# Expanders.net
KiCad netlist of a schematic drawn in Altium Designer
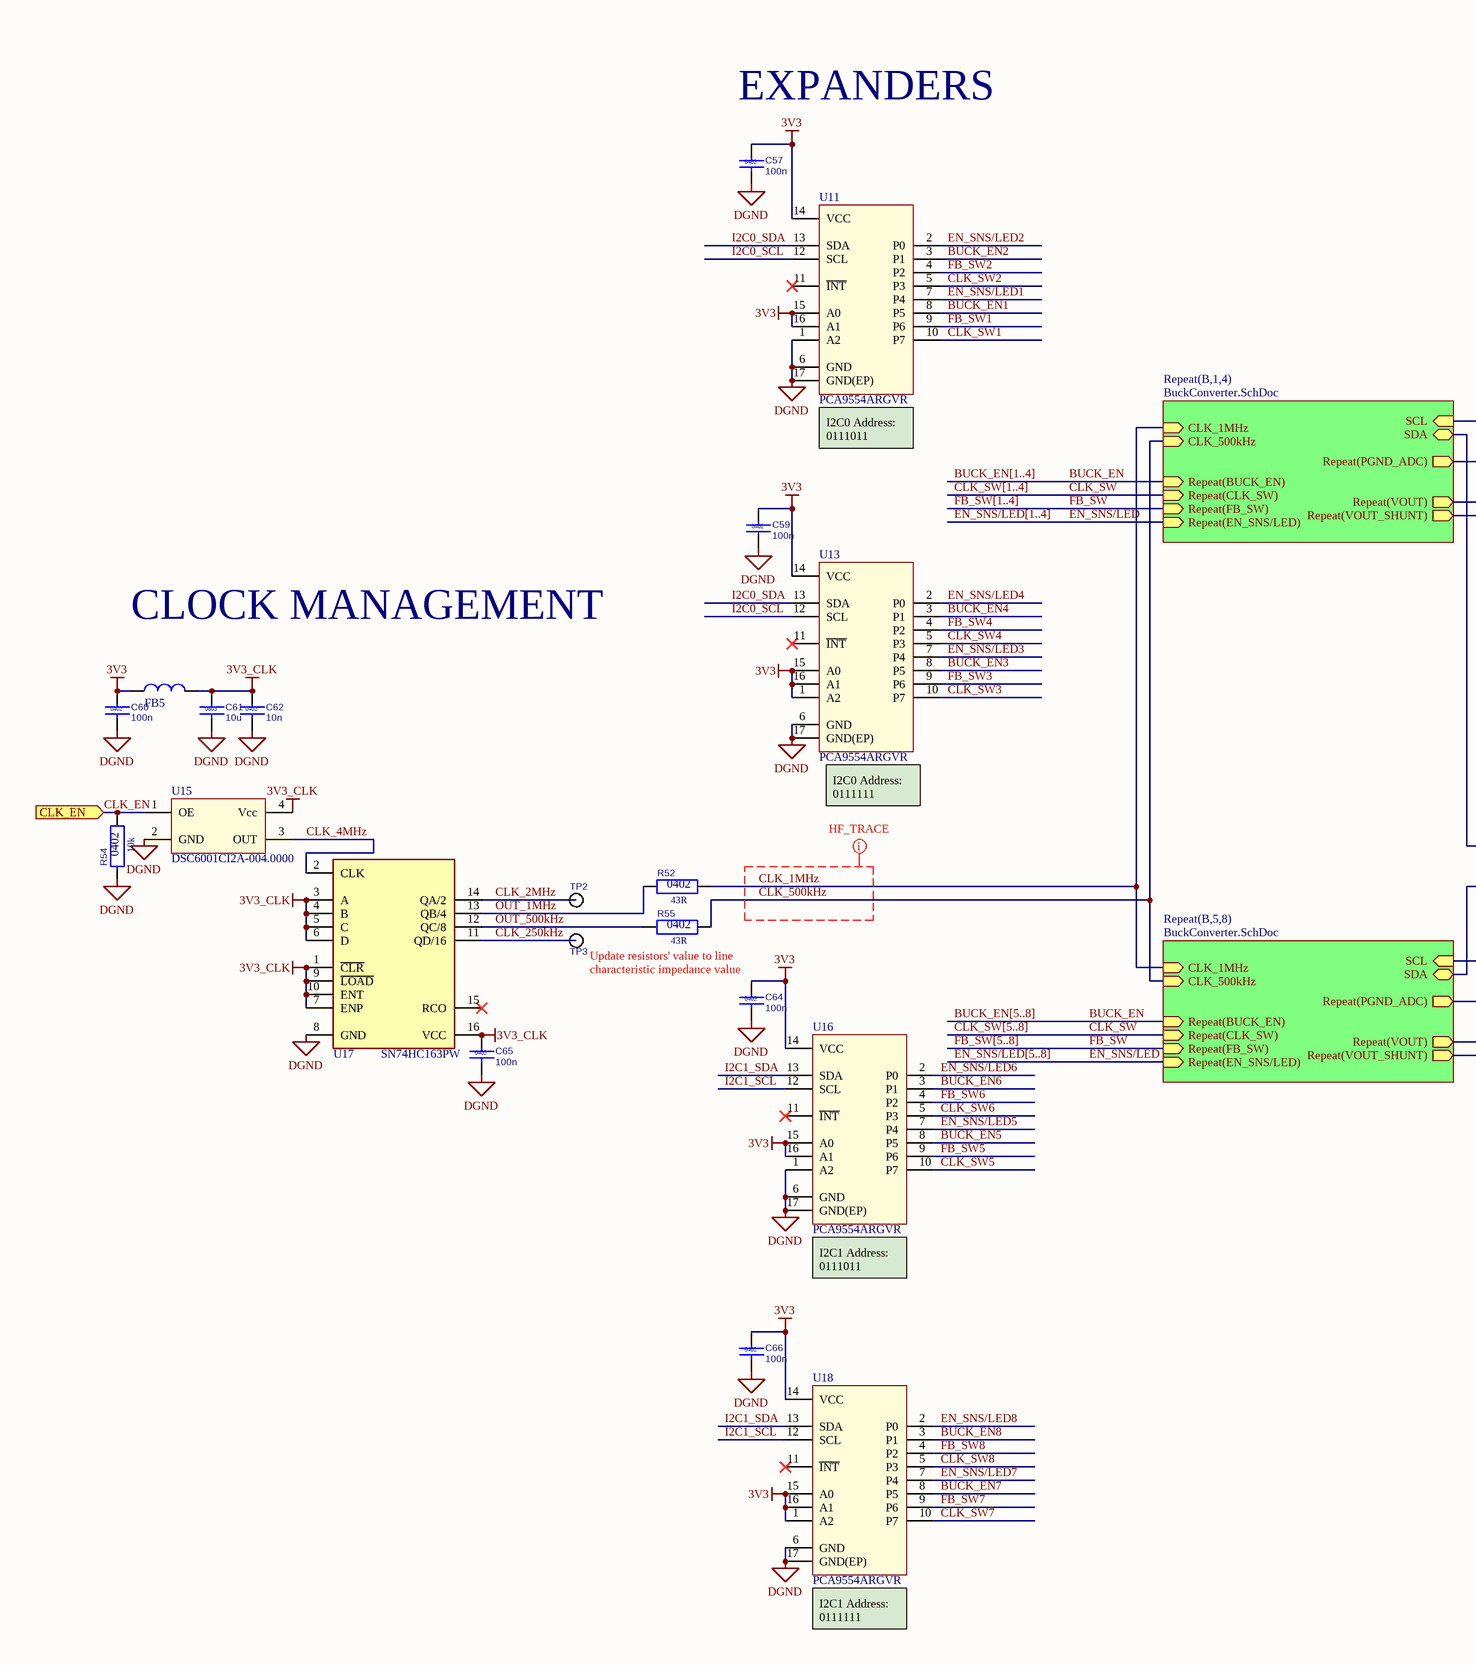
[diagram p0: Expanders.SchDoc, left]
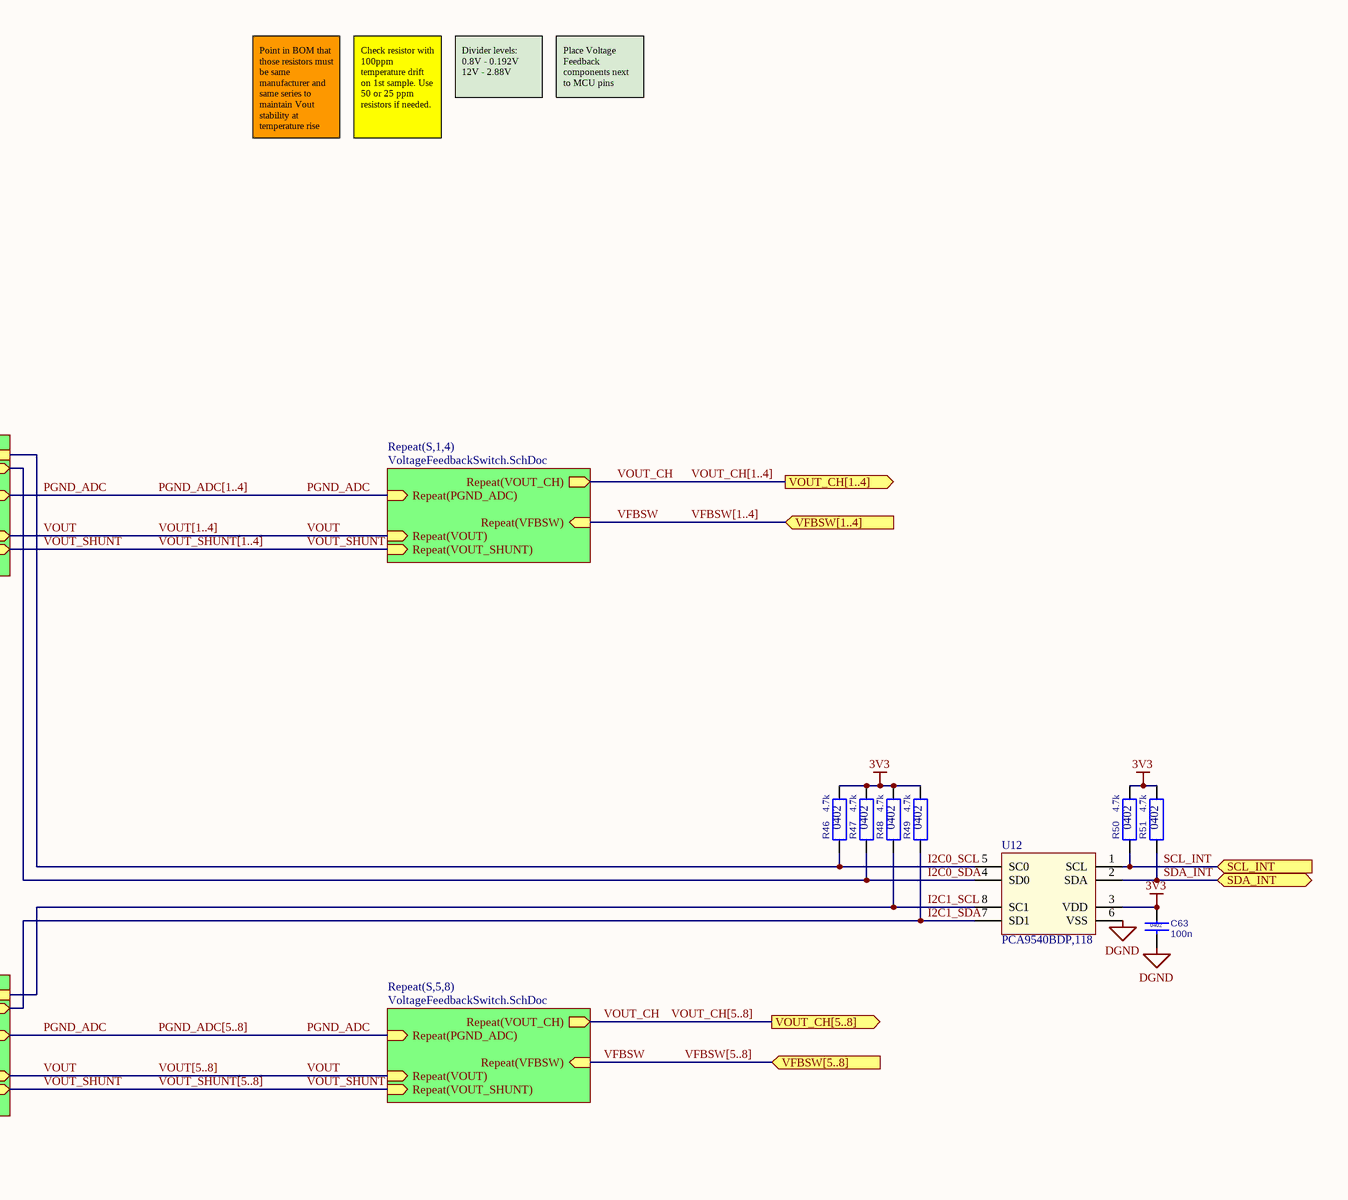
[diagram p1: Expanders.SchDoc, right]

(export (version "E")
  (design (tool "Eeschema 10.0.6"))
  (components
    (comp (ref "C57")
      (value "100n")
      (footprint "CC0402M")
      (description "Chip ceramic capacitor")
      (fields
        (field (name "CASE") "0402")
        (field (name "PARTNUMBER") "CC0402K-X7R-25V-100N-M")
        (field (name "MANUFACTURER") "Murata")
        (field (name "PUBLISHER") "alexey.savchenko")
      )
      (libsource (lib "AltiumLib") (part "Capacitor_nonpolar"))
    )
    (comp (ref "C59")
      (value "100n")
      (footprint "CC0402M")
      (description "Chip ceramic capacitor")
      (fields
        (field (name "CASE") "0402")
        (field (name "PARTNUMBER") "CC0402K-X7R-25V-100N-M")
        (field (name "MANUFACTURER") "Murata")
        (field (name "PUBLISHER") "alexey.savchenko")
      )
      (libsource (lib "AltiumLib") (part "Capacitor_nonpolar"))
    )
    (comp (ref "C60")
      (value "100n")
      (footprint "CC0402M")
      (description "Chip ceramic capacitor")
      (fields
        (field (name "CASE") "0402")
        (field (name "PARTNUMBER") "CC0402K-X7R-25V-100N-M")
        (field (name "MANUFACTURER") "Murata")
        (field (name "PUBLISHER") "alexey.savchenko")
      )
      (libsource (lib "AltiumLib") (part "Capacitor_nonpolar"))
    )
    (comp (ref "C61")
      (value "10u")
      (footprint "CC0805M")
      (description "Chip ceramic capacitor")
      (fields
        (field (name "CASE") "0805")
        (field (name "PARTNUMBER") "CC0805K-X7R-6V3-10U-M")
        (field (name "MANUFACTURER") "Samsung")
        (field (name "PUBLISHER") "alexey.savchenko")
      )
      (libsource (lib "AltiumLib") (part "Capacitor_nonpolar"))
    )
    (comp (ref "C62")
      (value "10n")
      (footprint "CC0402M")
      (description "Chip ceramic capacitor")
      (fields
        (field (name "CASE") "0402")
        (field (name "PARTNUMBER") "CC0402K-X7R-50V-10N-M")
        (field (name "MANUFACTURER") "Yageo")
        (field (name "PUBLISHER") "alexey.savchenko")
      )
      (libsource (lib "AltiumLib") (part "Capacitor_nonpolar"))
    )
    (comp (ref "C63")
      (value "100n")
      (footprint "CC0402M")
      (description "Chip ceramic capacitor")
      (fields
        (field (name "CASE") "0402")
        (field (name "PARTNUMBER") "CC0402K-X7R-25V-100N-M")
        (field (name "MANUFACTURER") "Murata")
        (field (name "PUBLISHER") "alexey.savchenko")
      )
      (libsource (lib "AltiumLib") (part "Capacitor_nonpolar"))
    )
    (comp (ref "C64")
      (value "100n")
      (footprint "CC0402M")
      (description "Chip ceramic capacitor")
      (fields
        (field (name "CASE") "0402")
        (field (name "PARTNUMBER") "CC0402K-X7R-25V-100N-M")
        (field (name "MANUFACTURER") "Murata")
        (field (name "PUBLISHER") "alexey.savchenko")
      )
      (libsource (lib "AltiumLib") (part "Capacitor_nonpolar"))
    )
    (comp (ref "C65")
      (value "100n")
      (footprint "CC0402M")
      (description "Chip ceramic capacitor")
      (fields
        (field (name "CASE") "0402")
        (field (name "PARTNUMBER") "CC0402K-X7R-25V-100N-M")
        (field (name "MANUFACTURER") "Murata")
        (field (name "PUBLISHER") "alexey.savchenko")
      )
      (libsource (lib "AltiumLib") (part "Capacitor_nonpolar"))
    )
    (comp (ref "C66")
      (value "100n")
      (footprint "CC0402M")
      (description "Chip ceramic capacitor")
      (fields
        (field (name "CASE") "0402")
        (field (name "PARTNUMBER") "CC0402K-X7R-25V-100N-M")
        (field (name "MANUFACTURER") "Murata")
        (field (name "PUBLISHER") "alexey.savchenko")
      )
      (libsource (lib "AltiumLib") (part "Capacitor_nonpolar"))
    )
    (comp (ref "FB5")
      (value "BLM18HG102SN1D")
      (footprint "FB0603M")
      (description "FERRITE BEAD 1 KOHM 0603 1LN")
      (fields (field (name "MANUFACTURER") "Murata") (field (name "PUBLISHER") "alexey.savchenko"))
      (libsource (lib "AltiumLib") (part "FerriteBead"))
    )
    (comp (ref "R46")
      (value "4.7k")
      (footprint "RC0402M")
      (description "Chip resistor")
      (fields
        (field (name "CASE") "0402")
        (field (name "PARTNUMBER") "RC0402F-4K7-M")
        (field (name "POWER") "0.063W")
        (field (name "PUBLISHER") "alexey.savchenko")
      )
      (libsource (lib "AltiumLib") (part "Resistor"))
    )
    (comp (ref "R47")
      (value "4.7k")
      (footprint "RC0402M")
      (description "Chip resistor")
      (fields
        (field (name "CASE") "0402")
        (field (name "PARTNUMBER") "RC0402F-4K7-M")
        (field (name "POWER") "0.063W")
        (field (name "PUBLISHER") "alexey.savchenko")
      )
      (libsource (lib "AltiumLib") (part "Resistor"))
    )
    (comp (ref "R48")
      (value "4.7k")
      (footprint "RC0402M")
      (description "Chip resistor")
      (fields
        (field (name "CASE") "0402")
        (field (name "PARTNUMBER") "RC0402F-4K7-M")
        (field (name "POWER") "0.063W")
        (field (name "PUBLISHER") "alexey.savchenko")
      )
      (libsource (lib "AltiumLib") (part "Resistor"))
    )
    (comp (ref "R49")
      (value "4.7k")
      (footprint "RC0402M")
      (description "Chip resistor")
      (fields
        (field (name "CASE") "0402")
        (field (name "PARTNUMBER") "RC0402F-4K7-M")
        (field (name "POWER") "0.063W")
        (field (name "PUBLISHER") "alexey.savchenko")
      )
      (libsource (lib "AltiumLib") (part "Resistor"))
    )
    (comp (ref "R50")
      (value "4.7k")
      (footprint "RC0402M")
      (description "Chip resistor")
      (fields
        (field (name "CASE") "0402")
        (field (name "PARTNUMBER") "RC0402F-4K7-M")
        (field (name "POWER") "0.063W")
        (field (name "PUBLISHER") "alexey.savchenko")
      )
      (libsource (lib "AltiumLib") (part "Resistor"))
    )
    (comp (ref "R51")
      (value "4.7k")
      (footprint "RC0402M")
      (description "Chip resistor")
      (fields
        (field (name "CASE") "0402")
        (field (name "PARTNUMBER") "RC0402F-4K7-M")
        (field (name "POWER") "0.063W")
        (field (name "PUBLISHER") "alexey.savchenko")
      )
      (libsource (lib "AltiumLib") (part "Resistor"))
    )
    (comp (ref "R52")
      (value "43R")
      (footprint "RC0402M")
      (description "Chip resistor")
      (fields
        (field (name "CASE") "0402")
        (field (name "PARTNUMBER") "RC0402F-43R-M")
        (field (name "POWER") "0.063W")
        (field (name "PUBLISHER") "alexey.savchenko")
      )
      (libsource (lib "AltiumLib") (part "Resistor"))
    )
    (comp (ref "R54")
      (value "10k")
      (footprint "RC0402M")
      (description "Chip resistor")
      (fields
        (field (name "CASE") "0402")
        (field (name "PARTNUMBER") "RC0402F-10K-M")
        (field (name "MANUFACTURER") "Yageo")
        (field (name "PUBLISHER") "alexey.savchenko")
      )
      (libsource (lib "AltiumLib") (part "Resistor"))
    )
    (comp (ref "R55")
      (value "43R")
      (footprint "RC0402M")
      (description "Chip resistor")
      (fields
        (field (name "CASE") "0402")
        (field (name "PARTNUMBER") "RC0402F-43R-M")
        (field (name "POWER") "0.063W")
        (field (name "PUBLISHER") "alexey.savchenko")
      )
      (libsource (lib "AltiumLib") (part "Resistor"))
    )
    (comp (ref "TP2")
      (value "TEST_POINT")
      (footprint "TEST_POINT_SMALL")
      (description "Test point")
      (fields
        (field (name "PARTNUMBER") "TEST_POINT_SMALL")
        (field (name "MANUFACTURER") "NULL")
        (field (name "PUBLISHER") "alexey.savchenko")
      )
      (libsource (lib "AltiumLib") (part "TEST_POINT"))
    )
    (comp (ref "TP3")
      (value "TEST_POINT")
      (footprint "TEST_POINT_SMALL")
      (description "Test point")
      (fields
        (field (name "PARTNUMBER") "TEST_POINT_SMALL")
        (field (name "MANUFACTURER") "NULL")
        (field (name "PUBLISHER") "alexey.savchenko")
      )
      (libsource (lib "AltiumLib") (part "TEST_POINT"))
    )
    (comp (ref "U11")
      (value "PCA9554ARGVR")
      (footprint "VQFN-16(RGV)")
      (description "I/O Expander 8 I²C, SMBus 400kHz 16-VQFN (4x4)")
      (fields (field (name "MANUFACTURER") "TI") (field (name "PUBLISHER") "alexey.savchenko"))
      (libsource (lib "AltiumLib") (part "PCA9554ARGVR"))
    )
    (comp (ref "U12")
      (value "PCA9540BDP,118")
      (footprint "TSSOP-8")
      (description "IC INTERFACE SPECIALIZED 8TSSOP")
      (fields (field (name "MANUFACTURER") "NXP") (field (name "PUBLISHER") "alexey.savchenko"))
      (libsource (lib "AltiumLib") (part "PCA9540B"))
    )
    (comp (ref "U13")
      (value "PCA9554ARGVR")
      (footprint "VQFN-16(RGV)")
      (description "I/O Expander 8 I²C, SMBus 400kHz 16-VQFN (4x4)")
      (fields (field (name "MANUFACTURER") "TI") (field (name "PUBLISHER") "alexey.savchenko"))
      (libsource (lib "AltiumLib") (part "PCA9554ARGVR"))
    )
    (comp (ref "U15")
      (value "DSC6001CI2A-004.0000")
      (footprint "CDFN3225-4LD")
      (description "4MHz XO (Standard) CMOS Oscillator 1.8V ~ 3.3V Enable/Disable 4-SMD, No Lead")
      (fields (field (name "MANUFACTURER") "Microchip") (field (name "PUBLISHER") "alexey.savchenko"))
      (libsource (lib "AltiumLib") (part "DSC6001"))
    )
    (comp (ref "U16")
      (value "PCA9554ARGVR")
      (footprint "VQFN-16(RGV)")
      (description "I/O Expander 8 I²C, SMBus 400kHz 16-VQFN (4x4)")
      (fields (field (name "MANUFACTURER") "TI") (field (name "PUBLISHER") "alexey.savchenko"))
      (libsource (lib "AltiumLib") (part "PCA9554ARGVR"))
    )
    (comp (ref "U17")
      (value "SN74HC163PW")
      (footprint "TSSOP-16")
      (description "Counter IC Binary Counter 1 Element 4 Bit Positive Edge 16-TSSOP")
      (fields (field (name "MANUFACTURER") "TI") (field (name "PUBLISHER") "alexey.savchenko"))
      (libsource (lib "AltiumLib") (part "74HC163PW"))
    )
    (comp (ref "U18")
      (value "PCA9554ARGVR")
      (footprint "VQFN-16(RGV)")
      (description "I/O Expander 8 I²C, SMBus 400kHz 16-VQFN (4x4)")
      (fields (field (name "MANUFACTURER") "TI") (field (name "PUBLISHER") "alexey.savchenko"))
      (libsource (lib "AltiumLib") (part "PCA9554ARGVR"))
    )
  )
  (nets
    (net (code "50") (name "/BUCK_EN1") (class "Default")
      (node (ref "U11") (pin "8") (pinfunction "P5_8") (pintype "passive"))
    )
    (net (code "51") (name "/BUCK_EN2") (class "Default")
      (node (ref "U11") (pin "3") (pinfunction "P1_3") (pintype "passive"))
    )
    (net (code "52") (name "/BUCK_EN3") (class "Default")
      (node (ref "U13") (pin "8") (pinfunction "P5_8") (pintype "passive"))
    )
    (net (code "53") (name "/BUCK_EN4") (class "Default")
      (node (ref "U13") (pin "3") (pinfunction "P1_3") (pintype "passive"))
    )
    (net (code "54") (name "/BUCK_EN5") (class "Default")
      (node (ref "U16") (pin "8") (pinfunction "P5_8") (pintype "passive"))
    )
    (net (code "55") (name "/BUCK_EN6") (class "Default")
      (node (ref "U16") (pin "3") (pinfunction "P1_3") (pintype "passive"))
    )
    (net (code "56") (name "/BUCK_EN7") (class "Default")
      (node (ref "U18") (pin "8") (pinfunction "P5_8") (pintype "passive"))
    )
    (net (code "57") (name "/BUCK_EN8") (class "Default")
      (node (ref "U18") (pin "3") (pinfunction "P1_3") (pintype "passive"))
    )
    (net (code "60") (name "/CLK_1MHz") (class "Default")
      (node (ref "R52") (pin "2") (pinfunction "2_2") (pintype "passive"))
    )
    (net (code "61") (name "/CLK_2MHz") (class "Default")
      (node (ref "TP2") (pin "0") (pinfunction "0_0") (pintype "passive"))
      (node (ref "U17") (pin "14") (pinfunction "QA/2_14") (pintype "passive"))
    )
    (net (code "62") (name "/CLK_4MHz") (class "Default")
      (node (ref "U15") (pin "3") (pinfunction "OUT_3") (pintype "passive"))
      (node (ref "U17") (pin "2") (pinfunction "CLK_2") (pintype "passive"))
    )
    (net (code "63") (name "/CLK_250kHz") (class "Default")
      (node (ref "TP3") (pin "0") (pinfunction "0_0") (pintype "passive"))
      (node (ref "U17") (pin "11") (pinfunction "QD/16_11") (pintype "passive"))
    )
    (net (code "64") (name "/CLK_500kHz") (class "Default")
      (node (ref "R55") (pin "2") (pinfunction "2_2") (pintype "passive"))
    )
    (net (code "65") (name "/CLK_EN") (class "Default")
      (node (ref "R54") (pin "2") (pinfunction "2_2") (pintype "passive"))
      (node (ref "U15") (pin "1") (pinfunction "OE_1") (pintype "passive"))
    )
    (net (code "67") (name "/CLK_SW1") (class "Default")
      (node (ref "U11") (pin "10") (pinfunction "P7_10") (pintype "passive"))
    )
    (net (code "68") (name "/CLK_SW2") (class "Default")
      (node (ref "U11") (pin "5") (pinfunction "P3_5") (pintype "passive"))
    )
    (net (code "69") (name "/CLK_SW3") (class "Default")
      (node (ref "U13") (pin "10") (pinfunction "P7_10") (pintype "passive"))
    )
    (net (code "70") (name "/CLK_SW4") (class "Default")
      (node (ref "U13") (pin "5") (pinfunction "P3_5") (pintype "passive"))
    )
    (net (code "71") (name "/CLK_SW5") (class "Default")
      (node (ref "U16") (pin "10") (pinfunction "P7_10") (pintype "passive"))
    )
    (net (code "72") (name "/CLK_SW6") (class "Default")
      (node (ref "U16") (pin "5") (pinfunction "P3_5") (pintype "passive"))
    )
    (net (code "73") (name "/CLK_SW7") (class "Default")
      (node (ref "U18") (pin "10") (pinfunction "P7_10") (pintype "passive"))
    )
    (net (code "74") (name "/CLK_SW8") (class "Default")
      (node (ref "U18") (pin "5") (pinfunction "P3_5") (pintype "passive"))
    )
    (net (code "78") (name "/EN_SNS{slash}LED1") (class "Default")
      (node (ref "U11") (pin "7") (pinfunction "P4_7") (pintype "passive"))
    )
    (net (code "79") (name "/EN_SNS{slash}LED2") (class "Default")
      (node (ref "U11") (pin "2") (pinfunction "P0_2") (pintype "passive"))
    )
    (net (code "80") (name "/EN_SNS{slash}LED3") (class "Default")
      (node (ref "U13") (pin "7") (pinfunction "P4_7") (pintype "passive"))
    )
    (net (code "81") (name "/EN_SNS{slash}LED4") (class "Default")
      (node (ref "U13") (pin "2") (pinfunction "P0_2") (pintype "passive"))
    )
    (net (code "82") (name "/EN_SNS{slash}LED5") (class "Default")
      (node (ref "U16") (pin "7") (pinfunction "P4_7") (pintype "passive"))
    )
    (net (code "83") (name "/EN_SNS{slash}LED6") (class "Default")
      (node (ref "U16") (pin "2") (pinfunction "P0_2") (pintype "passive"))
    )
    (net (code "84") (name "/EN_SNS{slash}LED7") (class "Default")
      (node (ref "U18") (pin "7") (pinfunction "P4_7") (pintype "passive"))
    )
    (net (code "85") (name "/EN_SNS{slash}LED8") (class "Default")
      (node (ref "U18") (pin "2") (pinfunction "P0_2") (pintype "passive"))
    )
    (net (code "89") (name "/FB_SW1") (class "Default")
      (node (ref "U11") (pin "9") (pinfunction "P6_9") (pintype "passive"))
    )
    (net (code "90") (name "/FB_SW2") (class "Default")
      (node (ref "U11") (pin "4") (pinfunction "P2_4") (pintype "passive"))
    )
    (net (code "91") (name "/FB_SW3") (class "Default")
      (node (ref "U13") (pin "9") (pinfunction "P6_9") (pintype "passive"))
    )
    (net (code "92") (name "/FB_SW4") (class "Default")
      (node (ref "U13") (pin "4") (pinfunction "P2_4") (pintype "passive"))
    )
    (net (code "93") (name "/FB_SW5") (class "Default")
      (node (ref "U16") (pin "9") (pinfunction "P6_9") (pintype "passive"))
    )
    (net (code "94") (name "/FB_SW6") (class "Default")
      (node (ref "U16") (pin "4") (pinfunction "P2_4") (pintype "passive"))
    )
    (net (code "95") (name "/FB_SW7") (class "Default")
      (node (ref "U18") (pin "9") (pinfunction "P6_9") (pintype "passive"))
    )
    (net (code "96") (name "/FB_SW8") (class "Default")
      (node (ref "U18") (pin "4") (pinfunction "P2_4") (pintype "passive"))
    )
    (net (code "99") (name "/I2C0_SCL") (class "Default")
      (node (ref "R46") (pin "1") (pinfunction "1_1") (pintype "passive"))
      (node (ref "U11") (pin "12") (pinfunction "SCL_12") (pintype "passive"))
      (node (ref "U12") (pin "5") (pinfunction "SC0_5") (pintype "passive"))
      (node (ref "U13") (pin "12") (pinfunction "SCL_12") (pintype "passive"))
    )
    (net (code "100") (name "/I2C0_SDA") (class "Default")
      (node (ref "R47") (pin "1") (pinfunction "1_1") (pintype "passive"))
      (node (ref "U11") (pin "13") (pinfunction "SDA_13") (pintype "passive"))
      (node (ref "U12") (pin "4") (pinfunction "SD0_4") (pintype "passive"))
      (node (ref "U13") (pin "13") (pinfunction "SDA_13") (pintype "passive"))
    )
    (net (code "101") (name "/I2C1_SCL") (class "Default")
      (node (ref "R48") (pin "1") (pinfunction "1_1") (pintype "passive"))
      (node (ref "U12") (pin "8") (pinfunction "SC1_8") (pintype "passive"))
      (node (ref "U16") (pin "12") (pinfunction "SCL_12") (pintype "passive"))
      (node (ref "U18") (pin "12") (pinfunction "SCL_12") (pintype "passive"))
    )
    (net (code "102") (name "/I2C1_SDA") (class "Default")
      (node (ref "R49") (pin "1") (pinfunction "1_1") (pintype "passive"))
      (node (ref "U12") (pin "7") (pinfunction "SD1_7") (pintype "passive"))
      (node (ref "U16") (pin "13") (pinfunction "SDA_13") (pintype "passive"))
      (node (ref "U18") (pin "13") (pinfunction "SDA_13") (pintype "passive"))
    )
    (net (code "103") (name "/OUT_1MHz") (class "Default")
      (node (ref "R52") (pin "1") (pinfunction "1_1") (pintype "passive"))
      (node (ref "U17") (pin "13") (pinfunction "QB/4_13") (pintype "passive"))
    )
    (net (code "104") (name "/OUT_500kHz") (class "Default")
      (node (ref "R55") (pin "1") (pinfunction "1_1") (pintype "passive"))
      (node (ref "U17") (pin "12") (pinfunction "QC/8_12") (pintype "passive"))
    )
    (net (code "108") (name "/SCL_INT") (class "Default")
      (node (ref "R50") (pin "1") (pinfunction "1_1") (pintype "passive"))
      (node (ref "U12") (pin "1") (pinfunction "SCL_1") (pintype "passive"))
    )
    (net (code "109") (name "/SDA_INT") (class "Default")
      (node (ref "R51") (pin "1") (pinfunction "1_1") (pintype "passive"))
      (node (ref "U12") (pin "2") (pinfunction "SDA_2") (pintype "passive"))
    )
    (net (code "122") (name "3V3") (class "Default")
      (node (ref "C57") (pin "1") (pinfunction "1_1") (pintype "passive"))
      (node (ref "C59") (pin "1") (pinfunction "1_1") (pintype "passive"))
      (node (ref "C60") (pin "1") (pinfunction "1_1") (pintype "passive"))
      (node (ref "C63") (pin "1") (pinfunction "1_1") (pintype "passive"))
      (node (ref "C64") (pin "1") (pinfunction "1_1") (pintype "passive"))
      (node (ref "C66") (pin "1") (pinfunction "1_1") (pintype "passive"))
      (node (ref "FB5") (pin "1") (pinfunction "1_1") (pintype "passive"))
      (node (ref "R46") (pin "2") (pinfunction "2_2") (pintype "passive"))
      (node (ref "R47") (pin "2") (pinfunction "2_2") (pintype "passive"))
      (node (ref "R48") (pin "2") (pinfunction "2_2") (pintype "passive"))
      (node (ref "R49") (pin "2") (pinfunction "2_2") (pintype "passive"))
      (node (ref "R50") (pin "2") (pinfunction "2_2") (pintype "passive"))
      (node (ref "R51") (pin "2") (pinfunction "2_2") (pintype "passive"))
      (node (ref "U11") (pin "14") (pinfunction "VCC_14") (pintype "passive"))
      (node (ref "U11") (pin "15") (pinfunction "A0_15") (pintype "passive"))
      (node (ref "U11") (pin "16") (pinfunction "A1_16") (pintype "passive"))
      (node (ref "U12") (pin "3") (pinfunction "VDD_3") (pintype "passive"))
      (node (ref "U13") (pin "1") (pinfunction "A2_1") (pintype "passive"))
      (node (ref "U13") (pin "14") (pinfunction "VCC_14") (pintype "passive"))
      (node (ref "U13") (pin "15") (pinfunction "A0_15") (pintype "passive"))
      (node (ref "U13") (pin "16") (pinfunction "A1_16") (pintype "passive"))
      (node (ref "U16") (pin "14") (pinfunction "VCC_14") (pintype "passive"))
      (node (ref "U16") (pin "15") (pinfunction "A0_15") (pintype "passive"))
      (node (ref "U16") (pin "16") (pinfunction "A1_16") (pintype "passive"))
      (node (ref "U18") (pin "1") (pinfunction "A2_1") (pintype "passive"))
      (node (ref "U18") (pin "14") (pinfunction "VCC_14") (pintype "passive"))
      (node (ref "U18") (pin "15") (pinfunction "A0_15") (pintype "passive"))
      (node (ref "U18") (pin "16") (pinfunction "A1_16") (pintype "passive"))
    )
    (net (code "123") (name "3V3_CLK") (class "Default")
      (node (ref "C61") (pin "1") (pinfunction "1_1") (pintype "passive"))
      (node (ref "C62") (pin "1") (pinfunction "1_1") (pintype "passive"))
      (node (ref "C65") (pin "1") (pinfunction "1_1") (pintype "passive"))
      (node (ref "FB5") (pin "2") (pinfunction "2_2") (pintype "passive"))
      (node (ref "U15") (pin "4") (pinfunction "Vcc_4") (pintype "passive"))
      (node (ref "U17") (pin "1") (pinfunction "~{CLR}_1") (pintype "passive"))
      (node (ref "U17") (pin "10") (pinfunction "ENT_10") (pintype "passive"))
      (node (ref "U17") (pin "16") (pinfunction "VCC_16") (pintype "passive"))
      (node (ref "U17") (pin "3") (pinfunction "A_3") (pintype "passive"))
      (node (ref "U17") (pin "4") (pinfunction "B_4") (pintype "passive"))
      (node (ref "U17") (pin "5") (pinfunction "C_5") (pintype "passive"))
      (node (ref "U17") (pin "6") (pinfunction "D_6") (pintype "passive"))
      (node (ref "U17") (pin "7") (pinfunction "ENP_7") (pintype "passive"))
      (node (ref "U17") (pin "9") (pinfunction "~{LOAD}_9") (pintype "passive"))
    )
    (net (code "124") (name "DGND") (class "Default")
      (node (ref "C57") (pin "2") (pinfunction "2_2") (pintype "passive"))
      (node (ref "C59") (pin "2") (pinfunction "2_2") (pintype "passive"))
      (node (ref "C60") (pin "2") (pinfunction "2_2") (pintype "passive"))
      (node (ref "C61") (pin "2") (pinfunction "2_2") (pintype "passive"))
      (node (ref "C62") (pin "2") (pinfunction "2_2") (pintype "passive"))
      (node (ref "C63") (pin "2") (pinfunction "2_2") (pintype "passive"))
      (node (ref "C64") (pin "2") (pinfunction "2_2") (pintype "passive"))
      (node (ref "C65") (pin "2") (pinfunction "2_2") (pintype "passive"))
      (node (ref "C66") (pin "2") (pinfunction "2_2") (pintype "passive"))
      (node (ref "R54") (pin "1") (pinfunction "1_1") (pintype "passive"))
      (node (ref "U11") (pin "1") (pinfunction "A2_1") (pintype "passive"))
      (node (ref "U11") (pin "17") (pinfunction "GND(EP)_17") (pintype "passive"))
      (node (ref "U11") (pin "6") (pinfunction "GND_6") (pintype "passive"))
      (node (ref "U12") (pin "6") (pinfunction "VSS_6") (pintype "passive"))
      (node (ref "U13") (pin "17") (pinfunction "GND(EP)_17") (pintype "passive"))
      (node (ref "U13") (pin "6") (pinfunction "GND_6") (pintype "passive"))
      (node (ref "U15") (pin "2") (pinfunction "GND_2") (pintype "passive"))
      (node (ref "U16") (pin "1") (pinfunction "A2_1") (pintype "passive"))
      (node (ref "U16") (pin "17") (pinfunction "GND(EP)_17") (pintype "passive"))
      (node (ref "U16") (pin "6") (pinfunction "GND_6") (pintype "passive"))
      (node (ref "U17") (pin "8") (pinfunction "GND_8") (pintype "passive"))
      (node (ref "U18") (pin "17") (pinfunction "GND(EP)_17") (pintype "passive"))
      (node (ref "U18") (pin "6") (pinfunction "GND_6") (pintype "passive"))
    )
    (net (code "125") (name "unconnected-(U11-~{INT}-Pad11)") (class "Default")
      (node (ref "U11") (pin "11") (pinfunction "~{INT}_11") (pintype "passive+no_connect"))
    )
    (net (code "126") (name "unconnected-(U13-~{INT}-Pad11)") (class "Default")
      (node (ref "U13") (pin "11") (pinfunction "~{INT}_11") (pintype "passive+no_connect"))
    )
    (net (code "127") (name "unconnected-(U16-~{INT}-Pad11)") (class "Default")
      (node (ref "U16") (pin "11") (pinfunction "~{INT}_11") (pintype "passive+no_connect"))
    )
    (net (code "128") (name "unconnected-(U17-RCO-Pad15)") (class "Default")
      (node (ref "U17") (pin "15") (pinfunction "RCO_15") (pintype "passive+no_connect"))
    )
    (net (code "129") (name "unconnected-(U18-~{INT}-Pad11)") (class "Default")
      (node (ref "U18") (pin "11") (pinfunction "~{INT}_11") (pintype "passive+no_connect"))
    )
  )
)
